# schematics.net
KiCad netlist of a schematic drawn in EAGLE
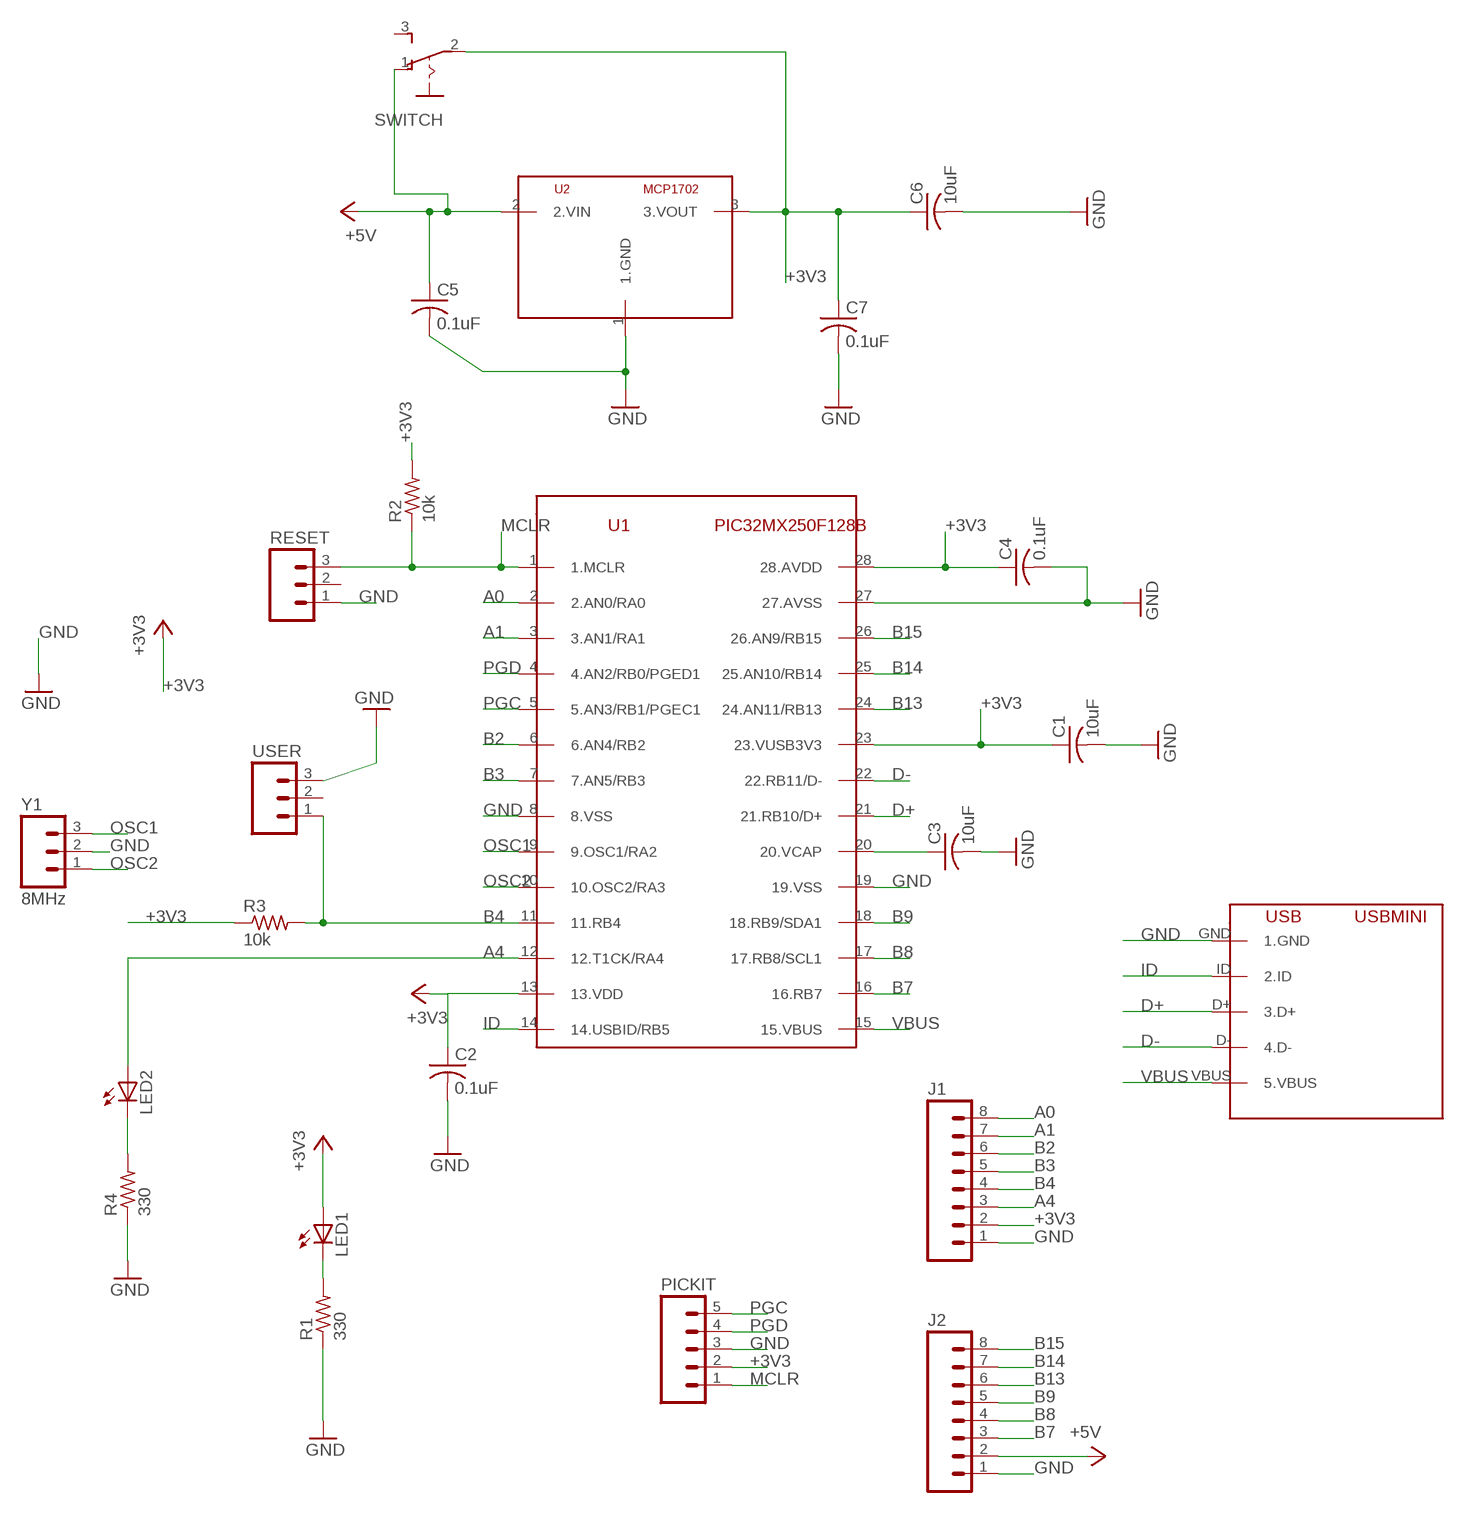
[diagram p0: schematic, sheet 1]

(export (version "E")
  (design (tool "Eeschema 10.0.6"))
  (components
    (comp (ref "C1")
      (value "10uF")
      (footprint "eagle-import:C025-024X044")
      (libsource (lib "eagle-import") (part "C-US025-024X044"))
    )
    (comp (ref "C2")
      (value "0.1uF")
      (footprint "eagle-import:C025-024X044")
      (libsource (lib "eagle-import") (part "C-US025-024X044"))
    )
    (comp (ref "C3")
      (value "10uF")
      (footprint "eagle-import:C025-024X044")
      (libsource (lib "eagle-import") (part "C-US025-024X044"))
    )
    (comp (ref "C4")
      (value "0.1uF")
      (footprint "eagle-import:C025-024X044")
      (libsource (lib "eagle-import") (part "C-US025-024X044"))
    )
    (comp (ref "C5")
      (value "0.1uF")
      (footprint "eagle-import:C025-024X044")
      (libsource (lib "eagle-import") (part "C-US025-024X044"))
    )
    (comp (ref "C6")
      (value "10uF")
      (footprint "eagle-import:C025-024X044")
      (libsource (lib "eagle-import") (part "C-US025-024X044"))
    )
    (comp (ref "C7")
      (value "0.1uF")
      (footprint "eagle-import:C025-024X044")
      (libsource (lib "eagle-import") (part "C-US025-024X044"))
    )
    (comp (ref "J1")
      (value "M08")
      (footprint "eagle-import:1X08_ROUND")
      (libsource (lib "eagle-import") (part "M08"))
    )
    (comp (ref "J2")
      (value "M08")
      (footprint "eagle-import:1X08_ROUND")
      (libsource (lib "eagle-import") (part "M08"))
    )
    (comp (ref "LED1")
      (value "LED3MM")
      (footprint "eagle-import:LED3MM")
      (libsource (lib "eagle-import") (part "LED3MM"))
    )
    (comp (ref "LED2")
      (value "LED3MM")
      (footprint "eagle-import:LED3MM")
      (libsource (lib "eagle-import") (part "LED3MM"))
    )
    (comp (ref "PICKIT")
      (value "M05PTH")
      (footprint "eagle-import:1X05")
      (libsource (lib "eagle-import") (part "M05PTH"))
    )
    (comp (ref "R1")
      (value "330")
      (footprint "eagle-import:0207_10")
      (libsource (lib "eagle-import") (part "resistor_R-US_0207/10"))
    )
    (comp (ref "R2")
      (value "10k")
      (footprint "eagle-import:0207_10")
      (libsource (lib "eagle-import") (part "R-US_0207/10"))
    )
    (comp (ref "R3")
      (value "10k")
      (footprint "eagle-import:0207_10")
      (libsource (lib "eagle-import") (part "R-US_0207/10"))
    )
    (comp (ref "R4")
      (value "330")
      (footprint "eagle-import:0207_10")
      (libsource (lib "eagle-import") (part "resistor_R-US_0207/10"))
    )
    (comp (ref "RESET")
      (value "M03PTH")
      (footprint "eagle-import:1X03")
      (libsource (lib "eagle-import") (part "M03PTH"))
    )
    (comp (ref "SWITCH")
      (value "255SB")
      (footprint "eagle-import:255SB")
      (libsource (lib "eagle-import") (part "255SB"))
    )
    (comp (ref "U1")
      (value "PIC32MX250F128B")
      (footprint "eagle-import:DIL28-3")
      (libsource (lib "eagle-import") (part "PIC32MX250F128B"))
    )
    (comp (ref "U2")
      (value "MCP1702")
      (footprint "eagle-import:TO92")
      (libsource (lib "eagle-import") (part "MCP1702"))
    )
    (comp (ref "USB")
      (value "USBMINI")
      (footprint "eagle-import:USB-MB-H")
      (libsource (lib "eagle-import") (part "USBMINI"))
    )
    (comp (ref "USER")
      (value "M03PTH")
      (footprint "eagle-import:1X03")
      (libsource (lib "eagle-import") (part "M03PTH"))
    )
    (comp (ref "Y1")
      (value "8MHz")
      (footprint "eagle-import:1X03")
      (libsource (lib "eagle-import") (part "M03PTH"))
    )
  )
  (nets
    (net (code "1") (name "+3V3") (class "Default")
      (node (ref "C1") (pin "1") (pinfunction "1_1") (pintype "passive"))
      (node (ref "C2") (pin "1") (pinfunction "1_1") (pintype "passive"))
      (node (ref "C4") (pin "1") (pinfunction "1_1") (pintype "passive"))
      (node (ref "C6") (pin "1") (pinfunction "1_1") (pintype "passive"))
      (node (ref "C7") (pin "1") (pinfunction "1_1") (pintype "passive"))
      (node (ref "J1") (pin "2") (pinfunction "2_2") (pintype "passive"))
      (node (ref "LED1") (pin "A") (pinfunction "A_A") (pintype "passive"))
      (node (ref "PICKIT") (pin "2") (pinfunction "2_2") (pintype "passive"))
      (node (ref "R2") (pin "2") (pinfunction "2_2") (pintype "passive"))
      (node (ref "R3") (pin "1") (pinfunction "1_1") (pintype "passive"))
      (node (ref "SWITCH") (pin "2") (pinfunction "P_2") (pintype "passive"))
      (node (ref "U1") (pin "13") (pinfunction "13.VDD_13") (pintype "bidirectional"))
      (node (ref "U1") (pin "23") (pinfunction "23.VUSB3V3_23") (pintype "bidirectional"))
      (node (ref "U1") (pin "28") (pinfunction "28.AVDD_28") (pintype "bidirectional"))
      (node (ref "U2") (pin "3") (pinfunction "3.VOUT_3") (pintype "bidirectional"))
    )
    (net (code "2") (name "+5V") (class "Default")
      (node (ref "C5") (pin "1") (pinfunction "1_1") (pintype "passive"))
      (node (ref "J2") (pin "2") (pinfunction "2_2") (pintype "passive"))
      (node (ref "SWITCH") (pin "1") (pinfunction "O_1") (pintype "passive"))
      (node (ref "U2") (pin "2") (pinfunction "2.VIN_2") (pintype "bidirectional"))
    )
    (net (code "3") (name "/A0") (class "Default")
      (node (ref "J1") (pin "8") (pinfunction "8_8") (pintype "passive"))
      (node (ref "U1") (pin "2") (pinfunction "2.AN0/RA0_2") (pintype "bidirectional"))
    )
    (net (code "4") (name "/A1") (class "Default")
      (node (ref "J1") (pin "7") (pinfunction "7_7") (pintype "passive"))
      (node (ref "U1") (pin "3") (pinfunction "3.AN1/RA1_3") (pintype "bidirectional"))
    )
    (net (code "5") (name "/A4") (class "Default")
      (node (ref "J1") (pin "3") (pinfunction "3_3") (pintype "passive"))
      (node (ref "LED2") (pin "A") (pinfunction "A_A") (pintype "passive"))
      (node (ref "U1") (pin "12") (pinfunction "12.T1CK/RA4_12") (pintype "bidirectional"))
    )
    (net (code "6") (name "/B2") (class "Default")
      (node (ref "J1") (pin "6") (pinfunction "6_6") (pintype "passive"))
      (node (ref "U1") (pin "6") (pinfunction "6.AN4/RB2_6") (pintype "bidirectional"))
    )
    (net (code "7") (name "/B3") (class "Default")
      (node (ref "J1") (pin "5") (pinfunction "5_5") (pintype "passive"))
      (node (ref "U1") (pin "7") (pinfunction "7.AN5/RB3_7") (pintype "bidirectional"))
    )
    (net (code "8") (name "/B4") (class "Default")
      (node (ref "J1") (pin "4") (pinfunction "4_4") (pintype "passive"))
      (node (ref "R3") (pin "2") (pinfunction "2_2") (pintype "passive"))
      (node (ref "U1") (pin "11") (pinfunction "11.RB4_11") (pintype "bidirectional"))
      (node (ref "USER") (pin "1") (pinfunction "1_1") (pintype "passive"))
    )
    (net (code "9") (name "/B7") (class "Default")
      (node (ref "J2") (pin "3") (pinfunction "3_3") (pintype "passive"))
      (node (ref "U1") (pin "16") (pinfunction "16.RB7_16") (pintype "bidirectional"))
    )
    (net (code "10") (name "/B8") (class "Default")
      (node (ref "J2") (pin "4") (pinfunction "4_4") (pintype "passive"))
      (node (ref "U1") (pin "17") (pinfunction "17.RB8/SCL1_17") (pintype "bidirectional"))
    )
    (net (code "11") (name "/B9") (class "Default")
      (node (ref "J2") (pin "5") (pinfunction "5_5") (pintype "passive"))
      (node (ref "U1") (pin "18") (pinfunction "18.RB9/SDA1_18") (pintype "bidirectional"))
    )
    (net (code "12") (name "/B13") (class "Default")
      (node (ref "J2") (pin "6") (pinfunction "6_6") (pintype "passive"))
      (node (ref "U1") (pin "24") (pinfunction "24.AN11/RB13_24") (pintype "bidirectional"))
    )
    (net (code "13") (name "/B14") (class "Default")
      (node (ref "J2") (pin "7") (pinfunction "7_7") (pintype "passive"))
      (node (ref "U1") (pin "25") (pinfunction "25.AN10/RB14_25") (pintype "bidirectional"))
    )
    (net (code "14") (name "/B15") (class "Default")
      (node (ref "J2") (pin "8") (pinfunction "8_8") (pintype "passive"))
      (node (ref "U1") (pin "26") (pinfunction "26.AN9/RB15_26") (pintype "bidirectional"))
    )
    (net (code "15") (name "/D+") (class "Default")
      (node (ref "U1") (pin "21") (pinfunction "21.RB10/D+_21") (pintype "bidirectional"))
      (node (ref "USB") (pin "D+") (pinfunction "3.D+_D+") (pintype "bidirectional"))
    )
    (net (code "16") (name "/D-") (class "Default")
      (node (ref "U1") (pin "22") (pinfunction "22.RB11/D-_22") (pintype "bidirectional"))
      (node (ref "USB") (pin "D-") (pinfunction "4.D-_D-") (pintype "bidirectional"))
    )
    (net (code "17") (name "/ID") (class "Default")
      (node (ref "U1") (pin "14") (pinfunction "14.USBID/RB5_14") (pintype "bidirectional"))
      (node (ref "USB") (pin "ID") (pinfunction "2.ID_ID") (pintype "bidirectional"))
    )
    (net (code "18") (name "/MCLR") (class "Default")
      (node (ref "PICKIT") (pin "1") (pinfunction "1_1") (pintype "passive"))
      (node (ref "R2") (pin "1") (pinfunction "1_1") (pintype "passive"))
      (node (ref "RESET") (pin "3") (pinfunction "3_3") (pintype "passive"))
      (node (ref "U1") (pin "1") (pinfunction "1.MCLR_1") (pintype "bidirectional"))
    )
    (net (code "19") (name "/OSC1") (class "Default")
      (node (ref "U1") (pin "9") (pinfunction "9.OSC1/RA2_9") (pintype "bidirectional"))
      (node (ref "Y1") (pin "3") (pinfunction "3_3") (pintype "passive"))
    )
    (net (code "20") (name "/OSC2") (class "Default")
      (node (ref "U1") (pin "10") (pinfunction "10.OSC2/RA3_10") (pintype "bidirectional"))
      (node (ref "Y1") (pin "1") (pinfunction "1_1") (pintype "passive"))
    )
    (net (code "21") (name "/PGC") (class "Default")
      (node (ref "PICKIT") (pin "5") (pinfunction "5_5") (pintype "passive"))
      (node (ref "U1") (pin "5") (pinfunction "5.AN3/RB1/PGEC1_5") (pintype "bidirectional"))
    )
    (net (code "22") (name "/PGD") (class "Default")
      (node (ref "PICKIT") (pin "4") (pinfunction "4_4") (pintype "passive"))
      (node (ref "U1") (pin "4") (pinfunction "4.AN2/RB0/PGED1_4") (pintype "bidirectional"))
    )
    (net (code "23") (name "/VBUS") (class "Default")
      (node (ref "U1") (pin "15") (pinfunction "15.VBUS_15") (pintype "bidirectional"))
      (node (ref "USB") (pin "VBUS") (pinfunction "5.VBUS_VBUS") (pintype "bidirectional"))
    )
    (net (code "24") (name "GND") (class "Default")
      (node (ref "C1") (pin "2") (pinfunction "2_2") (pintype "passive"))
      (node (ref "C2") (pin "2") (pinfunction "2_2") (pintype "passive"))
      (node (ref "C3") (pin "2") (pinfunction "2_2") (pintype "passive"))
      (node (ref "C4") (pin "2") (pinfunction "2_2") (pintype "passive"))
      (node (ref "C5") (pin "2") (pinfunction "2_2") (pintype "passive"))
      (node (ref "C6") (pin "2") (pinfunction "2_2") (pintype "passive"))
      (node (ref "C7") (pin "2") (pinfunction "2_2") (pintype "passive"))
      (node (ref "J1") (pin "1") (pinfunction "1_1") (pintype "passive"))
      (node (ref "J2") (pin "1") (pinfunction "1_1") (pintype "passive"))
      (node (ref "PICKIT") (pin "3") (pinfunction "3_3") (pintype "passive"))
      (node (ref "R1") (pin "1") (pinfunction "1_1") (pintype "passive"))
      (node (ref "R4") (pin "1") (pinfunction "1_1") (pintype "passive"))
      (node (ref "RESET") (pin "1") (pinfunction "1_1") (pintype "passive"))
      (node (ref "U1") (pin "19") (pinfunction "19.VSS_19") (pintype "bidirectional"))
      (node (ref "U1") (pin "27") (pinfunction "27.AVSS_27") (pintype "bidirectional"))
      (node (ref "U1") (pin "8") (pinfunction "8.VSS_8") (pintype "bidirectional"))
      (node (ref "U2") (pin "1") (pinfunction "1.GND_1") (pintype "bidirectional"))
      (node (ref "USB") (pin "GND") (pinfunction "1.GND_GND") (pintype "bidirectional"))
      (node (ref "USER") (pin "3") (pinfunction "3_3") (pintype "passive"))
      (node (ref "Y1") (pin "2") (pinfunction "2_2") (pintype "passive"))
    )
    (net (code "25") (name "Net-(LED1-C)") (class "Default")
      (node (ref "LED1") (pin "K") (pinfunction "C_K") (pintype "passive"))
      (node (ref "R1") (pin "2") (pinfunction "2_2") (pintype "passive"))
    )
    (net (code "26") (name "Net-(LED2-C)") (class "Default")
      (node (ref "LED2") (pin "K") (pinfunction "C_K") (pintype "passive"))
      (node (ref "R4") (pin "2") (pinfunction "2_2") (pintype "passive"))
    )
    (net (code "27") (name "Net-(U1-20.VCAP)") (class "Default")
      (node (ref "C3") (pin "1") (pinfunction "1_1") (pintype "passive"))
      (node (ref "U1") (pin "20") (pinfunction "20.VCAP_20") (pintype "bidirectional"))
    )
    (net (code "28") (name "unconnected-(RESET-Pad2)") (class "Default")
      (node (ref "RESET") (pin "2") (pinfunction "2_2") (pintype "passive"))
    )
    (net (code "29") (name "unconnected-(SWITCH-S-Pad3)") (class "Default")
      (node (ref "SWITCH") (pin "3") (pinfunction "S_3") (pintype "passive"))
    )
    (net (code "30") (name "unconnected-(USER-Pad2)") (class "Default")
      (node (ref "USER") (pin "2") (pinfunction "2_2") (pintype "passive"))
    )
  )
)
